# Smart_Extruder_Board.net
KiCad netlist of a schematic drawn in EAGLE
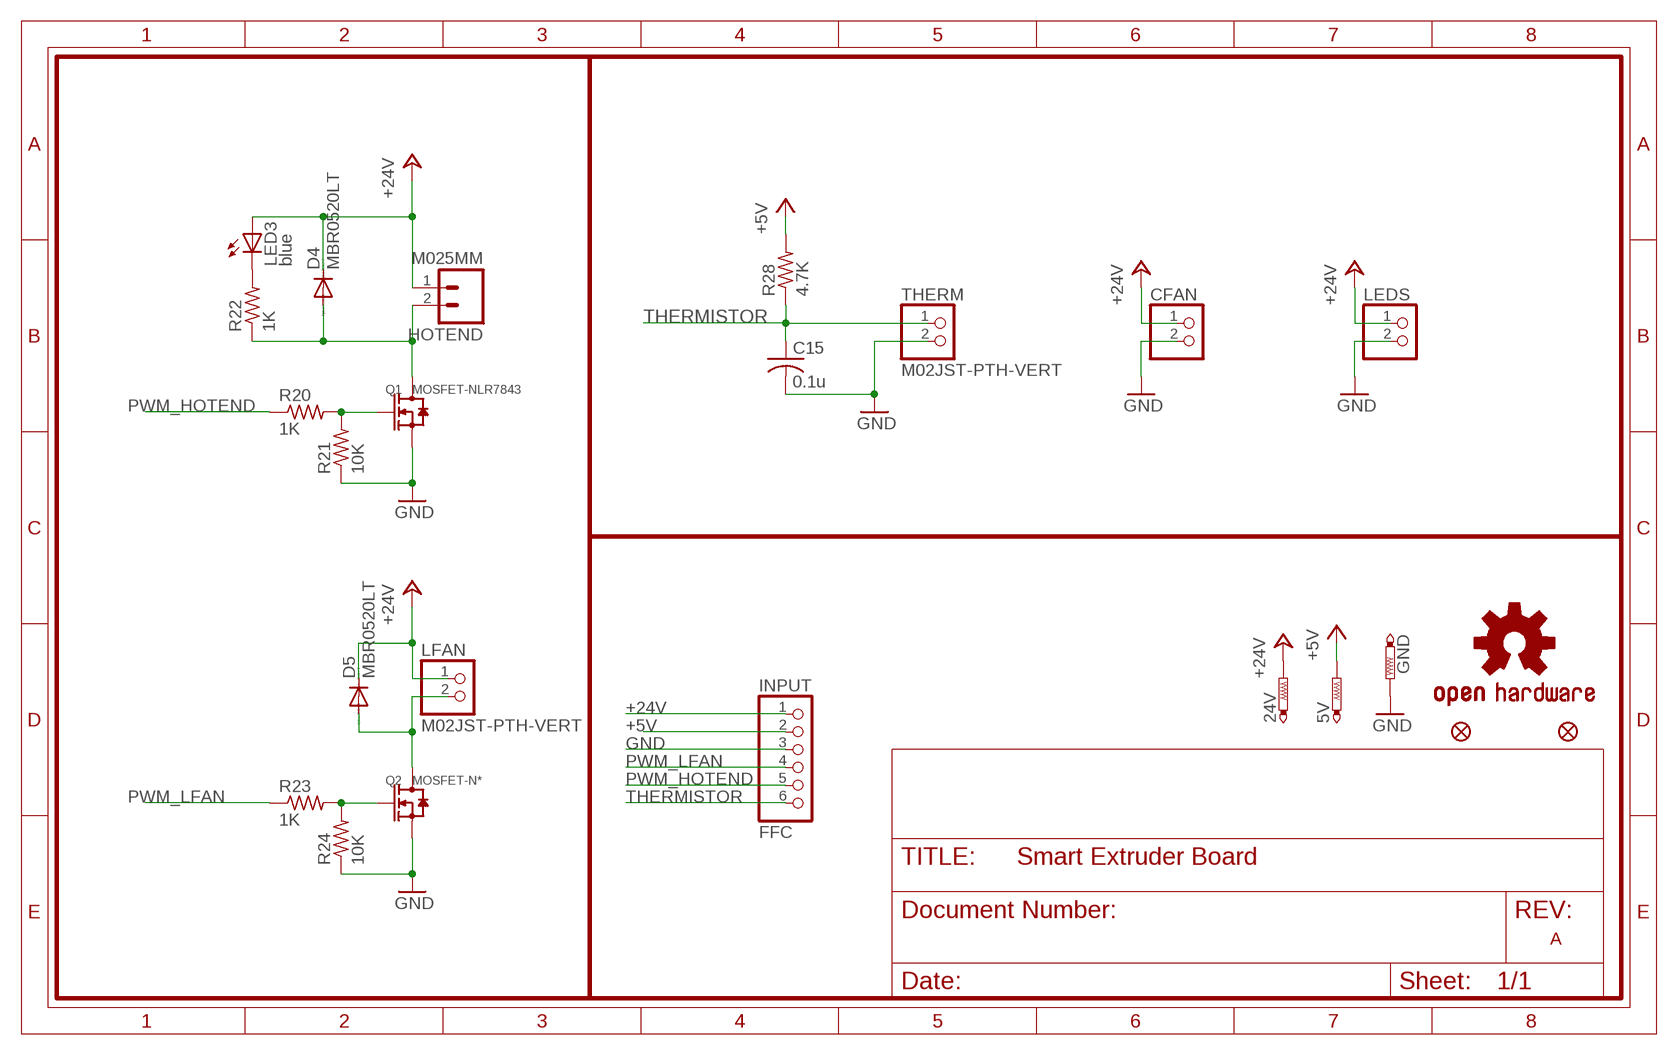
[diagram p0: schematic, sheet 1]

(export (version "E")
  (design (tool "Eeschema 10.0.6"))
  (components
    (comp (ref "5V")
      (value "PTR1TP10SQ")
      (footprint "eagle-import:TP10SQ")
      (libsource (lib "eagle-import") (part "PTR1TP10SQ"))
    )
    (comp (ref "24V")
      (value "PTR1TP10SQ")
      (footprint "eagle-import:TP10SQ")
      (libsource (lib "eagle-import") (part "PTR1TP10SQ"))
    )
    (comp (ref "C15")
      (value "0.1u")
      (footprint "eagle-import:C0805")
      (fields (field (name "MF") "AVX") (field (name "MPN") "08055C104KAT2A"))
      (libsource (lib "eagle-import") (part "C-USC0805"))
    )
    (comp (ref "CFAN")
      (value "PINHD-1X2/90")
      (footprint "eagle-import:1X02_90")
      (libsource (lib "eagle-import") (part "PINHD-1X2/90"))
    )
    (comp (ref "D4")
      (value "MBR0520LT")
      (footprint "eagle-import:SOD123")
      (fields (field (name "MF") "DIODES INC.") (field (name "MPN") "B0530W-7-F"))
      (libsource (lib "eagle-import") (part "MBR0520LT"))
    )
    (comp (ref "D5")
      (value "MBR0520LT")
      (footprint "eagle-import:SOD123")
      (fields (field (name "MF") "DIODES INC.") (field (name "MPN") "B0530W-7-F"))
      (libsource (lib "eagle-import") (part "MBR0520LT"))
    )
    (comp (ref "GND")
      (value "PTR1TP10SQ")
      (footprint "eagle-import:TP10SQ")
      (libsource (lib "eagle-import") (part "PTR1TP10SQ"))
    )
    (comp (ref "HOTEND")
      (value "M025MM")
      (footprint "eagle-import:SCREWTERMINAL-5MM-2")
      (libsource (lib "eagle-import") (part "M025MM"))
    )
    (comp (ref "INPUT")
      (value "FFC")
      (footprint "eagle-import:1X06_90")
      (libsource (lib "eagle-import") (part "PINHD-1X6/90"))
    )
    (comp (ref "JP1")
      (value "SPARKFUN_FIDUCIAL1X2.5")
      (footprint "eagle-import:SPARKFUN_FIDUCIAL-1X2.5")
      (libsource (lib "eagle-import") (part "SPARKFUN_FIDUCIAL1X2.5"))
    )
    (comp (ref "JP3")
      (value "SPARKFUN_FIDUCIAL1X2.5")
      (footprint "eagle-import:SPARKFUN_FIDUCIAL-1X2.5")
      (libsource (lib "eagle-import") (part "SPARKFUN_FIDUCIAL1X2.5"))
    )
    (comp (ref "LED3")
      (value "blue")
      (footprint "eagle-import:CHIP-LED0805")
      (fields (field (name "MF") "MULTICOMP") (field (name "MPN") "OVS-0803"))
      (libsource (lib "eagle-import") (part "LEDCHIP-LED0805"))
    )
    (comp (ref "LEDS")
      (value "PINHD-1X2/90")
      (footprint "eagle-import:1X02_90")
      (libsource (lib "eagle-import") (part "PINHD-1X2/90"))
    )
    (comp (ref "LFAN")
      (value "M02JST-PTH-VERT")
      (footprint "eagle-import:1X02_90")
      (libsource (lib "eagle-import") (part "PINHD-1X2/90"))
    )
    (comp (ref "LOGO1")
      (value "OSHW-LOGOS")
      (footprint "eagle-import:OSHW-LOGO-S")
      (libsource (lib "eagle-import") (part "OSHW-LOGOS"))
    )
    (comp (ref "Q1")
      (value "MOSFET-NLR7843")
      (footprint "eagle-import:TO252")
      (fields (field (name "MF") "INTERNATIONAL RECTIFIER") (field (name "MPN") "IRLR7843PBF"))
      (libsource (lib "eagle-import") (part "MOSFET-NLR7843"))
    )
    (comp (ref "Q2")
      (value "MOSFET-N*")
      (footprint "eagle-import:SOT23")
      (fields (field (name "MF") "INTERNATIONAL RECTIFIER") (field (name "MPN") "IRLML6344TRPBF"))
      (libsource (lib "eagle-import") (part "MOSFET-N"))
    )
    (comp (ref "R20")
      (value "1K")
      (footprint "eagle-import:M0805")
      (fields (field (name "MF") "BOURNS") (field (name "MPN") "CR0805-JW-102ELF"))
      (libsource (lib "eagle-import") (part "R-US_M0805"))
    )
    (comp (ref "R21")
      (value "10K")
      (footprint "eagle-import:M0805")
      (fields (field (name "MF") "BOURNS") (field (name "MPN") "CR0805-JW-103ELF"))
      (libsource (lib "eagle-import") (part "R-US_M0805"))
    )
    (comp (ref "R22")
      (value "1K")
      (footprint "eagle-import:M0805")
      (fields (field (name "MF") "BOURNS") (field (name "MPN") "CR0805-JW-102ELF"))
      (libsource (lib "eagle-import") (part "R-US_M0805"))
    )
    (comp (ref "R23")
      (value "1K")
      (footprint "eagle-import:M0805")
      (fields (field (name "MF") "BOURNS") (field (name "MPN") "CR0805-JW-102ELF"))
      (libsource (lib "eagle-import") (part "R-US_M0805"))
    )
    (comp (ref "R24")
      (value "10K")
      (footprint "eagle-import:M0805")
      (fields (field (name "MF") "BOURNS") (field (name "MPN") "CR0805-JW-103ELF"))
      (libsource (lib "eagle-import") (part "R-US_M0805"))
    )
    (comp (ref "R28")
      (value "4.7K")
      (footprint "eagle-import:M0805")
      (fields (field (name "MF") "BOURNS") (field (name "MPN") "CR0805-FX-4701GLF"))
      (libsource (lib "eagle-import") (part "R-US_M0805"))
    )
    (comp (ref "THERM")
      (value "M02JST-PTH-VERT")
      (footprint "eagle-import:1X02_90")
      (libsource (lib "eagle-import") (part "PINHD-1X2/90"))
    )
  )
  (nets
    (net (code "1") (name "+5V") (class "Default")
      (node (ref "5V") (pin "TP") (pinfunction "TP_TP") (pintype "input"))
      (node (ref "INPUT") (pin "2") (pinfunction "2_2") (pintype "passive"))
      (node (ref "R28") (pin "2") (pinfunction "2_2") (pintype "passive"))
    )
    (net (code "2") (name "+24V") (class "Default")
      (node (ref "24V") (pin "TP") (pinfunction "TP_TP") (pintype "input"))
      (node (ref "CFAN") (pin "1") (pinfunction "1_1") (pintype "passive"))
      (node (ref "D4") (pin "C") (pinfunction "C_C") (pintype "passive"))
      (node (ref "D5") (pin "C") (pinfunction "C_C") (pintype "passive"))
      (node (ref "HOTEND") (pin "1") (pinfunction "1_1") (pintype "passive"))
      (node (ref "INPUT") (pin "1") (pinfunction "1_1") (pintype "passive"))
      (node (ref "LED3") (pin "A") (pinfunction "A_A") (pintype "passive"))
      (node (ref "LEDS") (pin "1") (pinfunction "1_1") (pintype "passive"))
      (node (ref "LFAN") (pin "1") (pinfunction "1_1") (pintype "passive"))
    )
    (net (code "3") (name "/PWM_HOTEND") (class "Default")
      (node (ref "INPUT") (pin "5") (pinfunction "5_5") (pintype "passive"))
      (node (ref "R20") (pin "1") (pinfunction "1_1") (pintype "passive"))
    )
    (net (code "4") (name "/PWM_LFAN") (class "Default")
      (node (ref "INPUT") (pin "4") (pinfunction "4_4") (pintype "passive"))
      (node (ref "R23") (pin "1") (pinfunction "1_1") (pintype "passive"))
    )
    (net (code "5") (name "/THERMISTOR") (class "Default")
      (node (ref "C15") (pin "1") (pinfunction "1_1") (pintype "passive"))
      (node (ref "INPUT") (pin "6") (pinfunction "6_6") (pintype "passive"))
      (node (ref "R28") (pin "1") (pinfunction "1_1") (pintype "passive"))
      (node (ref "THERM") (pin "1") (pinfunction "1_1") (pintype "passive"))
    )
    (net (code "6") (name "GND") (class "Default")
      (node (ref "C15") (pin "2") (pinfunction "2_2") (pintype "passive"))
      (node (ref "CFAN") (pin "2") (pinfunction "2_2") (pintype "passive"))
      (node (ref "GND") (pin "TP") (pinfunction "TP_TP") (pintype "input"))
      (node (ref "INPUT") (pin "3") (pinfunction "3_3") (pintype "passive"))
      (node (ref "LEDS") (pin "2") (pinfunction "2_2") (pintype "passive"))
      (node (ref "Q1") (pin "2") (pinfunction "S_2") (pintype "passive"))
      (node (ref "Q2") (pin "2") (pinfunction "S_2") (pintype "passive"))
      (node (ref "R21") (pin "1") (pinfunction "1_1") (pintype "passive"))
      (node (ref "R24") (pin "1") (pinfunction "1_1") (pintype "passive"))
      (node (ref "THERM") (pin "2") (pinfunction "2_2") (pintype "passive"))
    )
    (net (code "7") (name "Net-(LED3-PadC)") (class "Default")
      (node (ref "LED3") (pin "C") (pinfunction "C_C") (pintype "passive"))
      (node (ref "R22") (pin "2") (pinfunction "2_2") (pintype "passive"))
    )
    (net (code "8") (name "Net-(Q1-D)") (class "Default")
      (node (ref "D4") (pin "A") (pinfunction "A_A") (pintype "passive"))
      (node (ref "HOTEND") (pin "2") (pinfunction "2_2") (pintype "passive"))
      (node (ref "Q1") (pin "3") (pinfunction "D_3") (pintype "passive"))
      (node (ref "R22") (pin "1") (pinfunction "1_1") (pintype "passive"))
    )
    (net (code "9") (name "Net-(Q1-G)") (class "Default")
      (node (ref "Q1") (pin "1") (pinfunction "G_1") (pintype "passive"))
      (node (ref "R20") (pin "2") (pinfunction "2_2") (pintype "passive"))
      (node (ref "R21") (pin "2") (pinfunction "2_2") (pintype "passive"))
    )
    (net (code "10") (name "Net-(Q2-D)") (class "Default")
      (node (ref "D5") (pin "A") (pinfunction "A_A") (pintype "passive"))
      (node (ref "LFAN") (pin "2") (pinfunction "2_2") (pintype "passive"))
      (node (ref "Q2") (pin "3") (pinfunction "D_3") (pintype "passive"))
    )
    (net (code "11") (name "Net-(Q2-G)") (class "Default")
      (node (ref "Q2") (pin "1") (pinfunction "G_1") (pintype "passive"))
      (node (ref "R23") (pin "2") (pinfunction "2_2") (pintype "passive"))
      (node (ref "R24") (pin "2") (pinfunction "2_2") (pintype "passive"))
    )
  )
)
